# xl4015.net
KiCad netlist of a schematic drawn in Altium Designer
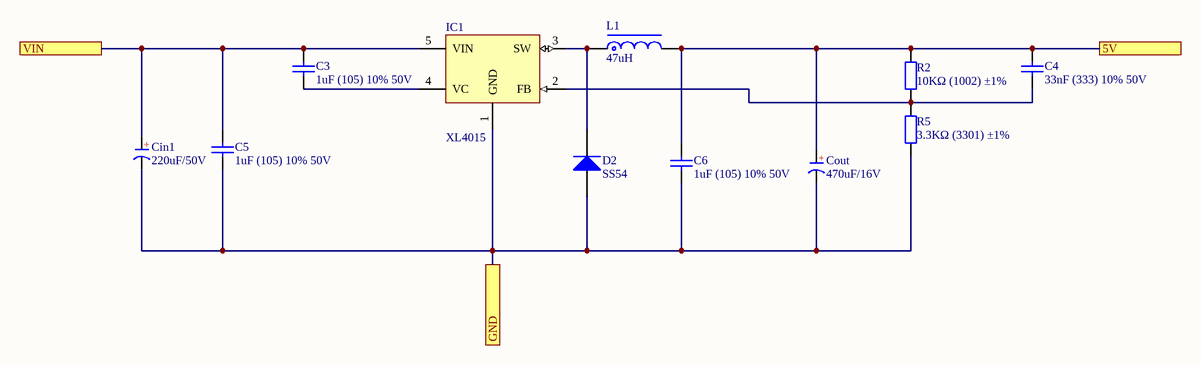
[diagram p0: xl4015.SchDoc]

(export (version "E")
  (design (tool "Eeschema 10.0.6"))
  (components
    (comp (ref "C3")
      (value "1uF (105) 10% 50V")
      (footprint "0805_C")
      (description "贴片电容")
      (libsource (lib "Miscellaneous Devices LC") (part "0805 1uF (105) 10% 50V"))
    )
    (comp (ref "C4")
      (value "33nF (333) 10% 50V")
      (footprint "0805_C")
      (description "贴片电容")
      (libsource (lib "Miscellaneous Devices LC") (part "0805 33nF (333) 10% 50V"))
    )
    (comp (ref "C5")
      (value "1uF (105) 10% 50V")
      (footprint "0805_C")
      (description "贴片电容")
      (libsource (lib "Miscellaneous Devices LC") (part "0805 1uF (105) 10% 50V"))
    )
    (comp (ref "C6")
      (value "1uF (105) 10% 50V")
      (footprint "0805_C")
      (description "贴片电容")
      (libsource (lib "Miscellaneous Devices LC") (part "0805 1uF (105) 10% 50V"))
    )
    (comp (ref "Cin1")
      (value "220uF/50V")
      (footprint "CM F(10*10.2)")
      (description "贴片电解电容")
      (fields (field (name "版权归属") "源创客"))
      (libsource (lib "3.1   - 电阻-电容-电感") (part "C-CM"))
    )
    (comp (ref "Cout")
      (value "470uF/16V")
      (footprint "CM E(8*10.2)")
      (description "贴片电解电容")
      (fields (field (name "版权归属") "源创客"))
      (libsource (lib "3.1   - 电阻-电容-电感") (part "C-CM"))
    )
    (comp (ref "D2")
      (value "SS54")
      (footprint "SMA(DO-214AC)_S1")
      (description "二极管")
      (libsource (lib "Miscellaneous Devices LC") (part "SMA(DO-214AC) SS54"))
    )
    (comp (ref "IC1")
      (value "XL4015")
      (footprint "TO263-5A")
      (description "DC降压芯片")
      (fields (field (name "版权归属") "源创客"))
      (libsource (lib "1.3   - 电源类芯片") (part "XL4015"))
    )
    (comp (ref "L1")
      (value "47uH")
      (footprint "CDRH127")
      (description "功率屏蔽电感")
      (fields (field (name "版权归属") "源创客"))
      (libsource (lib "3.1   - 电阻-电容-电感") (part "L-CDRH"))
    )
    (comp (ref "R2")
      (value "10KΩ (1002) ±1%")
      (footprint "0805_R")
      (description "贴片电阻")
      (libsource (lib "Miscellaneous Devices LC") (part "0805 10KΩ (1002) 1%"))
    )
    (comp (ref "R5")
      (value "3.3KΩ (3301) ±1%")
      (footprint "0805_R")
      (description "贴片电阻")
      (libsource (lib "Miscellaneous Devices LC") (part "0805 3.3KΩ (3301) 1%"))
    )
  )
  (nets
    (net (code "1") (name "/5V") (class "Default")
      (node (ref "C4") (pin "2") (pinfunction "2_2") (pintype "passive"))
      (node (ref "C6") (pin "2") (pinfunction "2_2") (pintype "passive"))
      (node (ref "Cout") (pin "1") (pinfunction "A_1") (pintype "passive"))
      (node (ref "L1") (pin "2") (pinfunction "2_2") (pintype "passive"))
      (node (ref "R2") (pin "2") (pinfunction "2_2") (pintype "passive"))
    )
    (net (code "2") (name "/GND") (class "Default")
      (node (ref "C5") (pin "1") (pinfunction "1_1") (pintype "passive"))
      (node (ref "C6") (pin "1") (pinfunction "1_1") (pintype "passive"))
      (node (ref "Cin1") (pin "2") (pinfunction "K_2") (pintype "passive"))
      (node (ref "Cout") (pin "2") (pinfunction "K_2") (pintype "passive"))
      (node (ref "D2") (pin "1") (pinfunction "A_1") (pintype "passive"))
      (node (ref "IC1") (pin "1") (pinfunction "GND_1") (pintype "power_in"))
      (node (ref "R5") (pin "1") (pinfunction "1_1") (pintype "passive"))
    )
    (net (code "3") (name "/VIN") (class "Default")
      (node (ref "C3") (pin "2") (pinfunction "2_2") (pintype "passive"))
      (node (ref "C5") (pin "2") (pinfunction "2_2") (pintype "passive"))
      (node (ref "Cin1") (pin "1") (pinfunction "A_1") (pintype "passive"))
      (node (ref "IC1") (pin "5") (pinfunction "VIN_5") (pintype "power_in"))
    )
    (net (code "4") (name "Net-(D2-K)") (class "Default")
      (node (ref "D2") (pin "2") (pinfunction "K_2") (pintype "passive"))
      (node (ref "IC1") (pin "3") (pinfunction "SW_3") (pintype "bidirectional"))
      (node (ref "L1") (pin "1") (pinfunction "1_1") (pintype "passive"))
    )
    (net (code "5") (name "Net-(IC1-FB)") (class "Default")
      (node (ref "C4") (pin "1") (pinfunction "1_1") (pintype "passive"))
      (node (ref "IC1") (pin "2") (pinfunction "FB_2") (pintype "input"))
      (node (ref "R2") (pin "1") (pinfunction "1_1") (pintype "passive"))
      (node (ref "R5") (pin "2") (pinfunction "2_2") (pintype "passive"))
    )
    (net (code "6") (name "Net-(IC1-VC)") (class "Default")
      (node (ref "C3") (pin "1") (pinfunction "1_1") (pintype "passive"))
      (node (ref "IC1") (pin "4") (pinfunction "VC_4") (pintype "passive"))
    )
  )
)
